# TS-ARM3_0_6.net
KiCad netlist of a schematic drawn in EAGLE
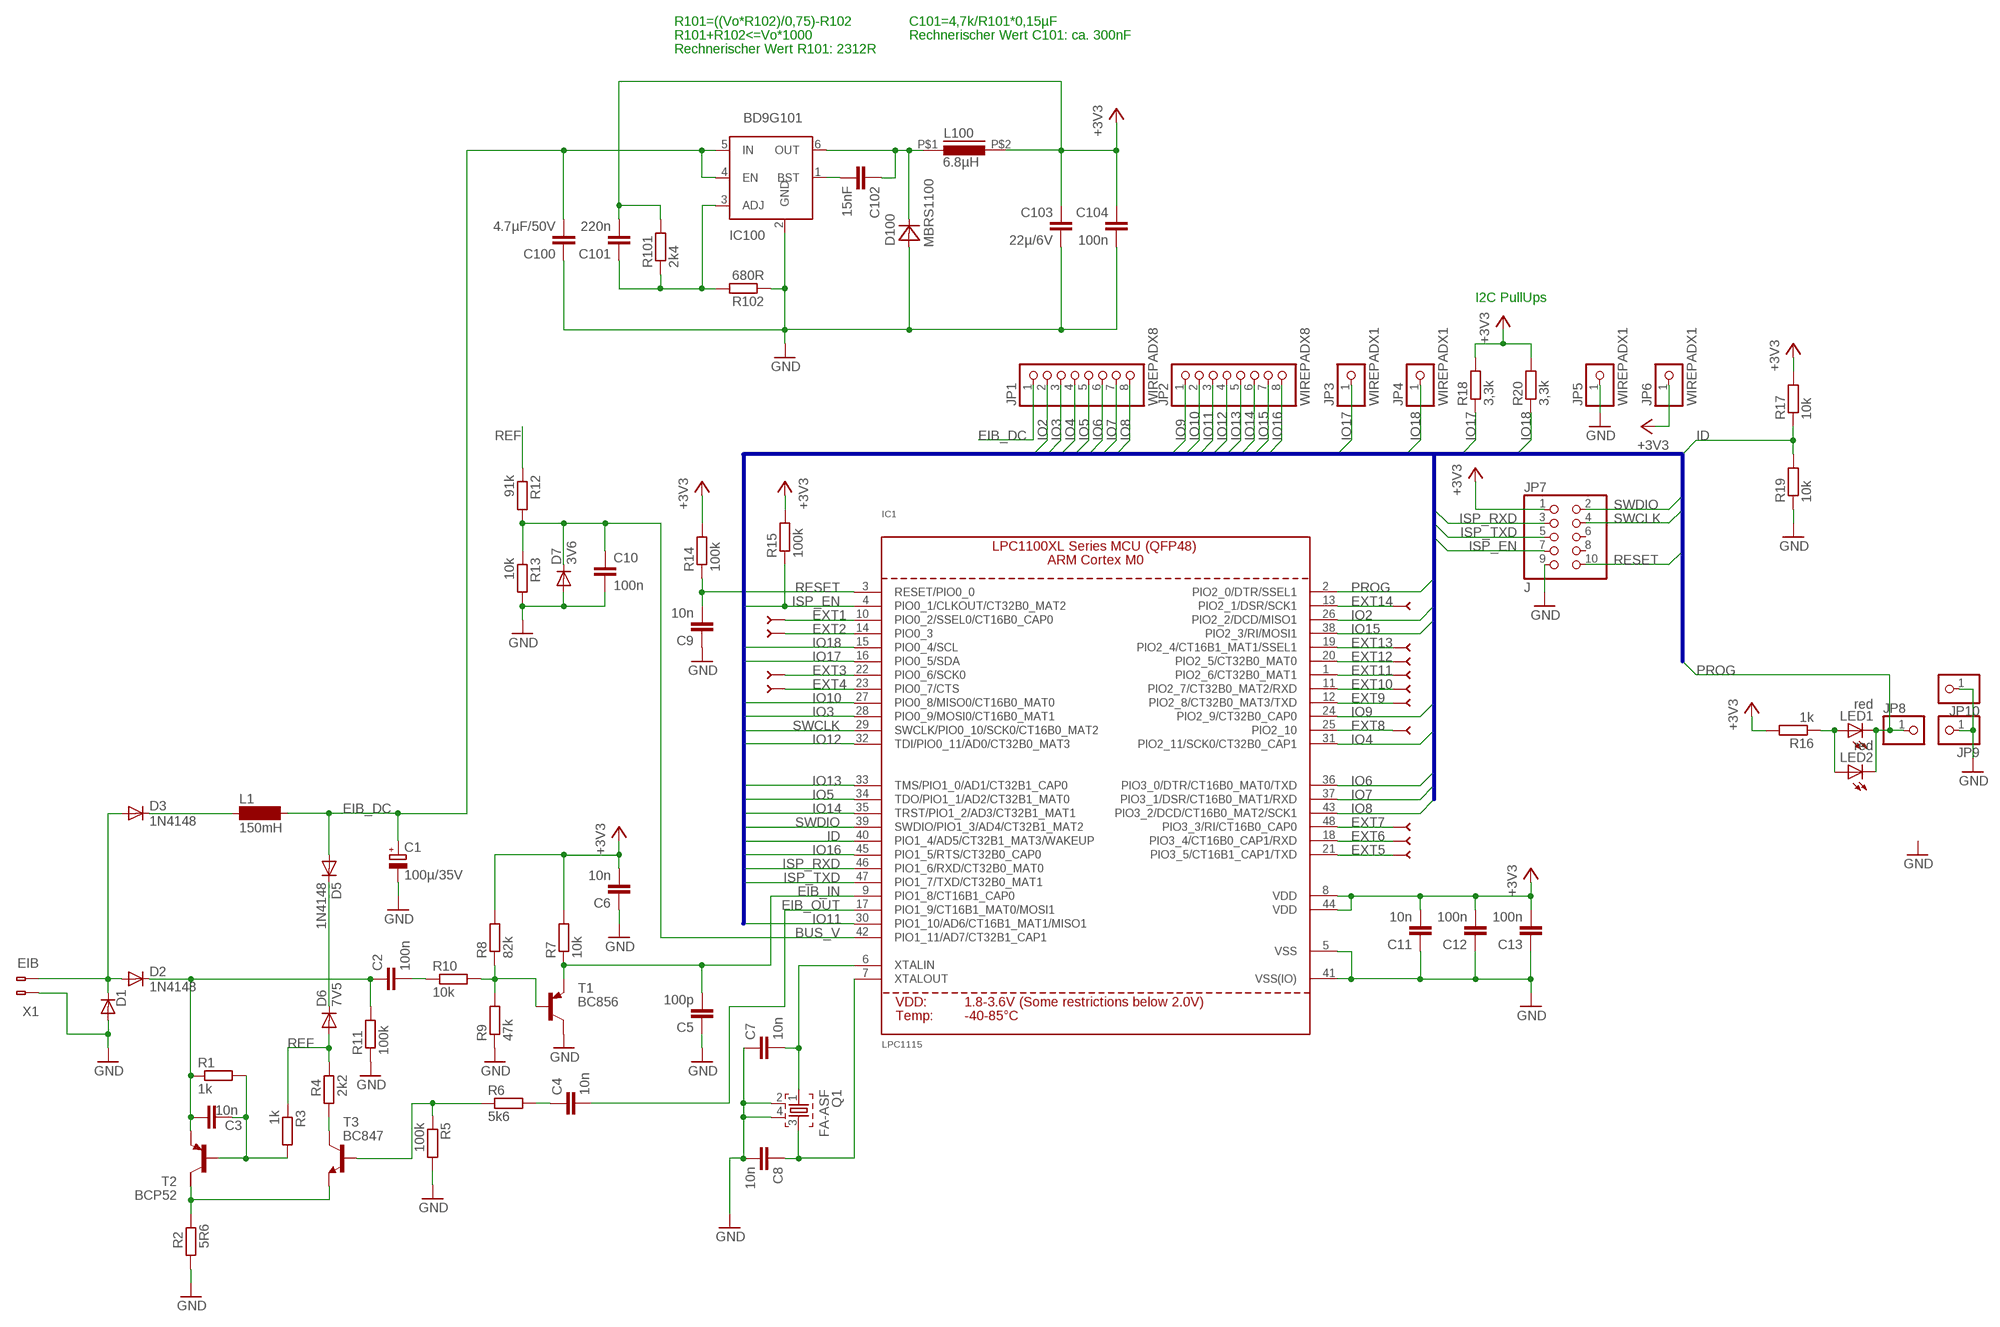
[diagram p0: schematic, sheet 1]

(export (version "E")
  (design (tool "Eeschema 10.0.6"))
  (components
    (comp (ref "C1")
      (value "100µ/35V")
      (footprint "eagle-import:SANYO-OSCON_SMD_C6")
      (libsource (lib "eagle-import") (part "CPOL-EUSANYO_SMD_C6"))
    )
    (comp (ref "C2")
      (value "100n")
      (footprint "eagle-import:C1206")
      (libsource (lib "eagle-import") (part "C-EUC1206"))
    )
    (comp (ref "C3")
      (value "10n")
      (footprint "eagle-import:C1206")
      (libsource (lib "eagle-import") (part "C-EUC1206"))
    )
    (comp (ref "C4")
      (value "10n")
      (footprint "eagle-import:C1206")
      (libsource (lib "eagle-import") (part "C-EUC1206"))
    )
    (comp (ref "C5")
      (value "100p")
      (footprint "eagle-import:C1206")
      (libsource (lib "eagle-import") (part "C-EUC1206"))
    )
    (comp (ref "C6")
      (value "10n")
      (footprint "eagle-import:C1206")
      (libsource (lib "eagle-import") (part "C-EUC1206"))
    )
    (comp (ref "C7")
      (value "10n")
      (footprint "eagle-import:C1206")
      (libsource (lib "eagle-import") (part "C-EUC1206"))
    )
    (comp (ref "C8")
      (value "10n")
      (footprint "eagle-import:C1206")
      (libsource (lib "eagle-import") (part "C-EUC1206"))
    )
    (comp (ref "C9")
      (value "10n")
      (footprint "eagle-import:C1206")
      (libsource (lib "eagle-import") (part "C-EUC1206"))
    )
    (comp (ref "C10")
      (value "100n")
      (footprint "eagle-import:C1206")
      (libsource (lib "eagle-import") (part "C-EUC1206"))
    )
    (comp (ref "C11")
      (value "10n")
      (footprint "eagle-import:C1206")
      (libsource (lib "eagle-import") (part "C-EUC1206"))
    )
    (comp (ref "C12")
      (value "100n")
      (footprint "eagle-import:C1206")
      (libsource (lib "eagle-import") (part "C-EUC1206"))
    )
    (comp (ref "C13")
      (value "100n")
      (footprint "eagle-import:C1206")
      (libsource (lib "eagle-import") (part "C-EUC1206"))
    )
    (comp (ref "C100")
      (value "4.7µF/50V")
      (footprint "eagle-import:C1206")
      (libsource (lib "eagle-import") (part "C-EUC1206"))
    )
    (comp (ref "C101")
      (value "220n")
      (footprint "eagle-import:C1206")
      (libsource (lib "eagle-import") (part "C-EUC1206"))
    )
    (comp (ref "C102")
      (value "15nF")
      (footprint "eagle-import:C1206")
      (libsource (lib "eagle-import") (part "C-EUC1206"))
    )
    (comp (ref "C103")
      (value "22µ/6V")
      (footprint "eagle-import:C1206")
      (libsource (lib "eagle-import") (part "C-EUC1206"))
    )
    (comp (ref "C104")
      (value "100n")
      (footprint "eagle-import:C1206")
      (libsource (lib "eagle-import") (part "C-EUC1206"))
    )
    (comp (ref "D1")
      (value "SMAJ40C")
      (footprint "eagle-import:SMB")
      (libsource (lib "eagle-import") (part "D-SMB"))
    )
    (comp (ref "D2")
      (value "1N4148")
      (footprint "eagle-import:MINIMELF")
      (libsource (lib "eagle-import") (part "DIODE-MINIMELF"))
    )
    (comp (ref "D3")
      (value "1N4148")
      (footprint "eagle-import:MINIMELF")
      (libsource (lib "eagle-import") (part "DIODE-MINIMELF"))
    )
    (comp (ref "D5")
      (value "1N4148")
      (footprint "eagle-import:MINIMELF")
      (libsource (lib "eagle-import") (part "DIODE-MINIMELF"))
    )
    (comp (ref "D6")
      (value "7V5")
      (footprint "eagle-import:MINIMELF")
      (libsource (lib "eagle-import") (part "DIODE-MINIMELF"))
    )
    (comp (ref "D7")
      (value "3V6")
      (footprint "eagle-import:MINIMELF")
      (libsource (lib "eagle-import") (part "DIODE-MINIMELF"))
    )
    (comp (ref "D100")
      (value "MBRS1100")
      (footprint "eagle-import:SMA")
      (libsource (lib "eagle-import") (part "MBRA340T3"))
    )
    (comp (ref "IC1")
      (value "LPC1115")
      (footprint "eagle-import:LQFP48")
      (libsource (lib "eagle-import") (part "LPC1113/4/5_QFP48_XLSERIES"))
    )
    (comp (ref "IC100")
      (value "BD9G101")
      (footprint "eagle-import:SOT23-6")
      (libsource (lib "eagle-import") (part "BD9G101GBD9G101G-SOT23-6"))
    )
    (comp (ref "JP1")
      (value "WIREPADX8")
      (footprint "eagle-import:SMD1,27X2,54X8")
      (libsource (lib "eagle-import") (part "WIREPADX8"))
    )
    (comp (ref "JP2")
      (value "WIREPADX8")
      (footprint "eagle-import:SMD1,27X2,54X8")
      (libsource (lib "eagle-import") (part "WIREPADX8"))
    )
    (comp (ref "JP3")
      (value "WIREPADX1")
      (footprint "eagle-import:SMD1,27X2,54")
      (libsource (lib "eagle-import") (part "WIREPADX1"))
    )
    (comp (ref "JP4")
      (value "WIREPADX1")
      (footprint "eagle-import:SMD1,27X2,54")
      (libsource (lib "eagle-import") (part "WIREPADX1"))
    )
    (comp (ref "JP5")
      (value "WIREPADX1")
      (footprint "eagle-import:SMD1,27X2,54")
      (libsource (lib "eagle-import") (part "WIREPADX1"))
    )
    (comp (ref "JP6")
      (value "WIREPADX1")
      (footprint "eagle-import:SMD1,27X2,54")
      (libsource (lib "eagle-import") (part "WIREPADX1"))
    )
    (comp (ref "JP7")
      (value "J")
      (footprint "eagle-import:2X05M")
      (libsource (lib "eagle-import") (part "PINHD-2X05_2.00"))
    )
    (comp (ref "JP8")
      (value "PINHD-1X1")
      (footprint "eagle-import:1X01")
      (libsource (lib "eagle-import") (part "PINHD-1X1"))
    )
    (comp (ref "JP9")
      (value "PINHD-1X1")
      (footprint "eagle-import:1X01")
      (libsource (lib "eagle-import") (part "PINHD-1X1"))
    )
    (comp (ref "JP10")
      (value "PINHD-1X1")
      (footprint "eagle-import:1X01")
      (libsource (lib "eagle-import") (part "PINHD-1X1"))
    )
    (comp (ref "L1")
      (value "150mH")
      (footprint "eagle-import:SD12_1000")
      (libsource (lib "eagle-import") (part "SD12-1000"))
    )
    (comp (ref "L100")
      (value "6.8µH")
      (footprint "eagle-import:PIS2812")
      (libsource (lib "eagle-import") (part "IND_FASTRON_1616FPS"))
    )
    (comp (ref "LED1")
      (value "red")
      (footprint "eagle-import:CHIPLED_1206")
      (libsource (lib "eagle-import") (part "LEDCHIPLED_1206"))
    )
    (comp (ref "LED2")
      (value "red")
      (footprint "eagle-import:LED3MM")
      (libsource (lib "eagle-import") (part "LED3MM"))
    )
    (comp (ref "P1")
      (value "PAD")
      (footprint "eagle-import:PAD")
      (libsource (lib "eagle-import") (part "PAD"))
    )
    (comp (ref "P2")
      (value "PAD")
      (footprint "eagle-import:PAD")
      (libsource (lib "eagle-import") (part "PAD"))
    )
    (comp (ref "P3")
      (value "PAD")
      (footprint "eagle-import:PAD")
      (libsource (lib "eagle-import") (part "PAD"))
    )
    (comp (ref "P4")
      (value "PAD")
      (footprint "eagle-import:PAD")
      (libsource (lib "eagle-import") (part "PAD"))
    )
    (comp (ref "P5")
      (value "PAD")
      (footprint "eagle-import:PAD")
      (libsource (lib "eagle-import") (part "PAD"))
    )
    (comp (ref "P6")
      (value "PAD")
      (footprint "eagle-import:PAD")
      (libsource (lib "eagle-import") (part "PAD"))
    )
    (comp (ref "P7")
      (value "PAD")
      (footprint "eagle-import:PAD")
      (libsource (lib "eagle-import") (part "PAD"))
    )
    (comp (ref "P8")
      (value "PAD")
      (footprint "eagle-import:PAD")
      (libsource (lib "eagle-import") (part "PAD"))
    )
    (comp (ref "P9")
      (value "PAD")
      (footprint "eagle-import:PAD")
      (libsource (lib "eagle-import") (part "PAD"))
    )
    (comp (ref "P10")
      (value "PAD")
      (footprint "eagle-import:PAD")
      (libsource (lib "eagle-import") (part "PAD"))
    )
    (comp (ref "P11")
      (value "PAD")
      (footprint "eagle-import:PAD")
      (libsource (lib "eagle-import") (part "PAD"))
    )
    (comp (ref "P12")
      (value "PAD")
      (footprint "eagle-import:PAD")
      (libsource (lib "eagle-import") (part "PAD"))
    )
    (comp (ref "P13")
      (value "PAD")
      (footprint "eagle-import:PAD")
      (libsource (lib "eagle-import") (part "PAD"))
    )
    (comp (ref "P14")
      (value "PAD")
      (footprint "eagle-import:PAD")
      (libsource (lib "eagle-import") (part "PAD"))
    )
    (comp (ref "Q1")
      (value "FA-ASF")
      (footprint "eagle-import:ASF")
      (libsource (lib "eagle-import") (part "FA-ASF"))
    )
    (comp (ref "R1")
      (value "1k")
      (footprint "eagle-import:R1206")
      (libsource (lib "eagle-import") (part "R-EU_R1206"))
    )
    (comp (ref "R2")
      (value "5R6")
      (footprint "eagle-import:R1206")
      (libsource (lib "eagle-import") (part "R-EU_R1206"))
    )
    (comp (ref "R3")
      (value "1k")
      (footprint "eagle-import:R1206")
      (libsource (lib "eagle-import") (part "R-EU_R1206"))
    )
    (comp (ref "R4")
      (value "2k2")
      (footprint "eagle-import:R1206")
      (libsource (lib "eagle-import") (part "R-EU_R1206"))
    )
    (comp (ref "R5")
      (value "100k")
      (footprint "eagle-import:R1206")
      (libsource (lib "eagle-import") (part "R-EU_R1206"))
    )
    (comp (ref "R6")
      (value "5k6")
      (footprint "eagle-import:R1206")
      (libsource (lib "eagle-import") (part "R-EU_R1206"))
    )
    (comp (ref "R7")
      (value "10k")
      (footprint "eagle-import:R1206")
      (libsource (lib "eagle-import") (part "R-EU_R1206"))
    )
    (comp (ref "R8")
      (value "82k")
      (footprint "eagle-import:R1206")
      (libsource (lib "eagle-import") (part "R-EU_R1206"))
    )
    (comp (ref "R9")
      (value "47k")
      (footprint "eagle-import:R1206")
      (libsource (lib "eagle-import") (part "R-EU_R1206"))
    )
    (comp (ref "R10")
      (value "10k")
      (footprint "eagle-import:R1206")
      (libsource (lib "eagle-import") (part "R-EU_R1206"))
    )
    (comp (ref "R11")
      (value "100k")
      (footprint "eagle-import:R1206")
      (libsource (lib "eagle-import") (part "R-EU_R1206"))
    )
    (comp (ref "R12")
      (value "91k")
      (footprint "eagle-import:R1206")
      (libsource (lib "eagle-import") (part "R-EU_R1206"))
    )
    (comp (ref "R13")
      (value "10k")
      (footprint "eagle-import:R1206")
      (libsource (lib "eagle-import") (part "R-EU_R1206"))
    )
    (comp (ref "R14")
      (value "100k")
      (footprint "eagle-import:R1206")
      (libsource (lib "eagle-import") (part "R-EU_R1206"))
    )
    (comp (ref "R15")
      (value "100k")
      (footprint "eagle-import:R1206")
      (libsource (lib "eagle-import") (part "R-EU_R1206"))
    )
    (comp (ref "R16")
      (value "1k")
      (footprint "eagle-import:R1206")
      (libsource (lib "eagle-import") (part "R-EU_R1206"))
    )
    (comp (ref "R17")
      (value "10k")
      (footprint "eagle-import:R1206")
      (libsource (lib "eagle-import") (part "R-EU_R1206"))
    )
    (comp (ref "R18")
      (value "3,3k")
      (footprint "eagle-import:R1206")
      (libsource (lib "eagle-import") (part "R-EU_R1206"))
    )
    (comp (ref "R19")
      (value "10k")
      (footprint "eagle-import:R1206")
      (libsource (lib "eagle-import") (part "R-EU_R1206"))
    )
    (comp (ref "R20")
      (value "3,3k")
      (footprint "eagle-import:R1206")
      (libsource (lib "eagle-import") (part "R-EU_R1206"))
    )
    (comp (ref "R101")
      (value "2k4")
      (footprint "eagle-import:R1206")
      (libsource (lib "eagle-import") (part "R-EU_R1206"))
    )
    (comp (ref "R102")
      (value "680R")
      (footprint "eagle-import:R1206")
      (libsource (lib "eagle-import") (part "R-EU_R1206"))
    )
    (comp (ref "T1")
      (value "BC856")
      (footprint "eagle-import:SOT23-BEC")
      (libsource (lib "eagle-import") (part "BC856SMDB"))
    )
    (comp (ref "T2")
      (value "BCP52")
      (footprint "eagle-import:SOT223")
      (libsource (lib "eagle-import") (part "FZT753SMD"))
    )
    (comp (ref "T3")
      (value "BC847")
      (footprint "eagle-import:SOT23")
      (libsource (lib "eagle-import") (part "BC847"))
    )
    (comp (ref "X1")
      (value "EIB")
      (footprint "eagle-import:BUSKLEMME243-724")
      (libsource (lib "eagle-import") (part "EIB"))
    )
  )
  (nets
    (net (code "1") (name "+3V3") (class "Default")
      (node (ref "C101") (pin "2") (pinfunction "2_2") (pintype "passive"))
      (node (ref "C103") (pin "1") (pinfunction "1_1") (pintype "passive"))
      (node (ref "C104") (pin "1") (pinfunction "1_1") (pintype "passive"))
      (node (ref "C11") (pin "2") (pinfunction "2_2") (pintype "passive"))
      (node (ref "C12") (pin "2") (pinfunction "2_2") (pintype "passive"))
      (node (ref "C13") (pin "2") (pinfunction "2_2") (pintype "passive"))
      (node (ref "C6") (pin "2") (pinfunction "2_2") (pintype "passive"))
      (node (ref "IC1") (pin "44") (pinfunction "VDD_44") (pintype "power_in"))
      (node (ref "IC1") (pin "8") (pinfunction "VDD_8") (pintype "power_in"))
      (node (ref "JP6") (pin "1") (pinfunction "1_1") (pintype "passive"))
      (node (ref "JP7") (pin "1") (pinfunction "1_1") (pintype "passive"))
      (node (ref "L100") (pin "P$2") (pinfunction "2_P$2") (pintype "passive"))
      (node (ref "R101") (pin "2") (pinfunction "2_2") (pintype "passive"))
      (node (ref "R14") (pin "2") (pinfunction "2_2") (pintype "passive"))
      (node (ref "R15") (pin "2") (pinfunction "2_2") (pintype "passive"))
      (node (ref "R16") (pin "2") (pinfunction "2_2") (pintype "passive"))
      (node (ref "R17") (pin "2") (pinfunction "2_2") (pintype "passive"))
      (node (ref "R18") (pin "2") (pinfunction "2_2") (pintype "passive"))
      (node (ref "R20") (pin "2") (pinfunction "2_2") (pintype "passive"))
      (node (ref "R7") (pin "2") (pinfunction "2_2") (pintype "passive"))
      (node (ref "R8") (pin "2") (pinfunction "2_2") (pintype "passive"))
    )
    (net (code "2") (name "/BUS_V") (class "Default")
      (node (ref "C10") (pin "2") (pinfunction "2_2") (pintype "passive"))
      (node (ref "D7") (pin "C") (pinfunction "C_C") (pintype "passive"))
      (node (ref "IC1") (pin "42") (pinfunction "PIO1_11/AD7/CT32B1_CAP1_42") (pintype "bidirectional"))
      (node (ref "R12") (pin "2") (pinfunction "2_2") (pintype "passive"))
      (node (ref "R13") (pin "1") (pinfunction "1_1") (pintype "passive"))
    )
    (net (code "3") (name "/EIB_DC") (class "Default")
      (node (ref "C1") (pin "+") (pinfunction "+_+") (pintype "passive"))
      (node (ref "C100") (pin "2") (pinfunction "2_2") (pintype "passive"))
      (node (ref "D5") (pin "A") (pinfunction "A_A") (pintype "passive"))
      (node (ref "IC100") (pin "4") (pinfunction "EN_4") (pintype "input"))
      (node (ref "IC100") (pin "5") (pinfunction "IN_5") (pintype "input"))
      (node (ref "JP1") (pin "1") (pinfunction "1_1") (pintype "passive"))
      (node (ref "L1") (pin "2") (pinfunction "2_2") (pintype "passive"))
    )
    (net (code "4") (name "/EIB_IN") (class "Default")
      (node (ref "C5") (pin "2") (pinfunction "2_2") (pintype "passive"))
      (node (ref "IC1") (pin "9") (pinfunction "PIO1_8/CT16B1_CAP0_9") (pintype "bidirectional"))
      (node (ref "R7") (pin "1") (pinfunction "1_1") (pintype "passive"))
      (node (ref "T1") (pin "E") (pinfunction "E_E") (pintype "passive"))
    )
    (net (code "5") (name "/EIB_OUT") (class "Default")
      (node (ref "C4") (pin "2") (pinfunction "2_2") (pintype "passive"))
      (node (ref "IC1") (pin "17") (pinfunction "PIO1_9/CT16B1_MAT0/MOSI1_17") (pintype "bidirectional"))
    )
    (net (code "6") (name "/EXT1") (class "Default")
      (node (ref "IC1") (pin "10") (pinfunction "PIO0_2/SSEL0/CT16B0_CAP0_10") (pintype "bidirectional"))
      (node (ref "P1") (pin "1") (pinfunction "1_1") (pintype "bidirectional"))
    )
    (net (code "7") (name "/EXT2") (class "Default")
      (node (ref "IC1") (pin "14") (pinfunction "PIO0_3_14") (pintype "bidirectional"))
      (node (ref "P2") (pin "1") (pinfunction "1_1") (pintype "bidirectional"))
    )
    (net (code "8") (name "/EXT3") (class "Default")
      (node (ref "IC1") (pin "22") (pinfunction "PIO0_6/SCK0_22") (pintype "bidirectional"))
      (node (ref "P13") (pin "1") (pinfunction "1_1") (pintype "bidirectional"))
    )
    (net (code "9") (name "/EXT4") (class "Default")
      (node (ref "IC1") (pin "23") (pinfunction "PIO0_7/CTS_23") (pintype "bidirectional"))
      (node (ref "P14") (pin "1") (pinfunction "1_1") (pintype "bidirectional"))
    )
    (net (code "10") (name "/EXT5") (class "Default")
      (node (ref "IC1") (pin "21") (pinfunction "PIO3_5/CT16B1_CAP1/TXD_21") (pintype "bidirectional"))
      (node (ref "P12") (pin "1") (pinfunction "1_1") (pintype "bidirectional"))
    )
    (net (code "11") (name "/EXT6") (class "Default")
      (node (ref "IC1") (pin "18") (pinfunction "PIO3_4/CT16B0_CAP1/RXD_18") (pintype "bidirectional"))
      (node (ref "P11") (pin "1") (pinfunction "1_1") (pintype "bidirectional"))
    )
    (net (code "12") (name "/EXT7") (class "Default")
      (node (ref "IC1") (pin "48") (pinfunction "PIO3_3/RI/CT16B0_CAP0_48") (pintype "bidirectional"))
      (node (ref "P10") (pin "1") (pinfunction "1_1") (pintype "bidirectional"))
    )
    (net (code "13") (name "/EXT8") (class "Default")
      (node (ref "IC1") (pin "25") (pinfunction "PIO2_10_25") (pintype "bidirectional"))
      (node (ref "P6") (pin "1") (pinfunction "1_1") (pintype "bidirectional"))
    )
    (net (code "14") (name "/EXT9") (class "Default")
      (node (ref "IC1") (pin "12") (pinfunction "PIO2_8/CT32B0_MAT3/TXD_12") (pintype "bidirectional"))
      (node (ref "P4") (pin "1") (pinfunction "1_1") (pintype "bidirectional"))
    )
    (net (code "15") (name "/EXT10") (class "Default")
      (node (ref "IC1") (pin "11") (pinfunction "PIO2_7/CT32B0_MAT2/RXD_11") (pintype "bidirectional"))
      (node (ref "P5") (pin "1") (pinfunction "1_1") (pintype "bidirectional"))
    )
    (net (code "16") (name "/EXT11") (class "Default")
      (node (ref "IC1") (pin "1") (pinfunction "PIO2_6/CT32B0_MAT1_1") (pintype "bidirectional"))
      (node (ref "P9") (pin "1") (pinfunction "1_1") (pintype "bidirectional"))
    )
    (net (code "17") (name "/EXT12") (class "Default")
      (node (ref "IC1") (pin "20") (pinfunction "PIO2_5/CT32B0_MAT0_20") (pintype "bidirectional"))
      (node (ref "P8") (pin "1") (pinfunction "1_1") (pintype "bidirectional"))
    )
    (net (code "18") (name "/EXT13") (class "Default")
      (node (ref "IC1") (pin "19") (pinfunction "PIO2_4/CT16B1_MAT1/SSEL1_19") (pintype "bidirectional"))
      (node (ref "P7") (pin "1") (pinfunction "1_1") (pintype "bidirectional"))
    )
    (net (code "19") (name "/EXT14") (class "Default")
      (node (ref "IC1") (pin "13") (pinfunction "PIO2_1/DSR/SCK1_13") (pintype "bidirectional"))
      (node (ref "P3") (pin "1") (pinfunction "1_1") (pintype "bidirectional"))
    )
    (net (code "20") (name "/ID") (class "Default")
      (node (ref "IC1") (pin "40") (pinfunction "PIO1_4/AD5/CT32B1_MAT3/WAKEUP_40") (pintype "bidirectional"))
      (node (ref "R17") (pin "1") (pinfunction "1_1") (pintype "passive"))
      (node (ref "R19") (pin "2") (pinfunction "2_2") (pintype "passive"))
    )
    (net (code "21") (name "/IO2") (class "Default")
      (node (ref "IC1") (pin "26") (pinfunction "PIO2_2/DCD/MISO1_26") (pintype "bidirectional"))
      (node (ref "JP1") (pin "2") (pinfunction "2_2") (pintype "passive"))
    )
    (net (code "22") (name "/IO3") (class "Default")
      (node (ref "IC1") (pin "28") (pinfunction "PIO0_9/MOSI0/CT16B0_MAT1_28") (pintype "bidirectional"))
      (node (ref "JP1") (pin "3") (pinfunction "3_3") (pintype "passive"))
    )
    (net (code "23") (name "/IO4") (class "Default")
      (node (ref "IC1") (pin "31") (pinfunction "PIO2_11/SCK0/CT32B0_CAP1_31") (pintype "bidirectional"))
      (node (ref "JP1") (pin "4") (pinfunction "4_4") (pintype "passive"))
    )
    (net (code "24") (name "/IO5") (class "Default")
      (node (ref "IC1") (pin "34") (pinfunction "TDO/PIO1_1/AD2/CT32B1_MAT0_34") (pintype "bidirectional"))
      (node (ref "JP1") (pin "5") (pinfunction "5_5") (pintype "passive"))
    )
    (net (code "25") (name "/IO6") (class "Default")
      (node (ref "IC1") (pin "36") (pinfunction "PIO3_0/DTR/CT16B0_MAT0/TXD_36") (pintype "bidirectional"))
      (node (ref "JP1") (pin "6") (pinfunction "6_6") (pintype "passive"))
    )
    (net (code "26") (name "/IO7") (class "Default")
      (node (ref "IC1") (pin "37") (pinfunction "PIO3_1/DSR/CT16B0_MAT1/RXD_37") (pintype "bidirectional"))
      (node (ref "JP1") (pin "7") (pinfunction "7_7") (pintype "passive"))
    )
    (net (code "27") (name "/IO8") (class "Default")
      (node (ref "IC1") (pin "43") (pinfunction "PIO3_2/DCD/CT16B0_MAT2/SCK1_43") (pintype "bidirectional"))
      (node (ref "JP1") (pin "8") (pinfunction "8_8") (pintype "passive"))
    )
    (net (code "28") (name "/IO9") (class "Default")
      (node (ref "IC1") (pin "24") (pinfunction "PIO2_9/CT32B0_CAP0_24") (pintype "bidirectional"))
      (node (ref "JP2") (pin "1") (pinfunction "1_1") (pintype "passive"))
    )
    (net (code "29") (name "/IO10") (class "Default")
      (node (ref "IC1") (pin "27") (pinfunction "PIO0_8/MISO0/CT16B0_MAT0_27") (pintype "bidirectional"))
      (node (ref "JP2") (pin "2") (pinfunction "2_2") (pintype "passive"))
    )
    (net (code "30") (name "/IO11") (class "Default")
      (node (ref "IC1") (pin "30") (pinfunction "PIO1_10/AD6/CT16B1_MAT1/MISO1_30") (pintype "bidirectional"))
      (node (ref "JP2") (pin "3") (pinfunction "3_3") (pintype "passive"))
    )
    (net (code "31") (name "/IO12") (class "Default")
      (node (ref "IC1") (pin "32") (pinfunction "TDI/PIO0_11/AD0/CT32B0_MAT3_32") (pintype "bidirectional"))
      (node (ref "JP2") (pin "4") (pinfunction "4_4") (pintype "passive"))
    )
    (net (code "32") (name "/IO13") (class "Default")
      (node (ref "IC1") (pin "33") (pinfunction "TMS/PIO1_0/AD1/CT32B1_CAP0_33") (pintype "bidirectional"))
      (node (ref "JP2") (pin "5") (pinfunction "5_5") (pintype "passive"))
    )
    (net (code "33") (name "/IO14") (class "Default")
      (node (ref "IC1") (pin "35") (pinfunction "TRST/PIO1_2/AD3/CT32B1_MAT1_35") (pintype "bidirectional"))
      (node (ref "JP2") (pin "6") (pinfunction "6_6") (pintype "passive"))
    )
    (net (code "34") (name "/IO15") (class "Default")
      (node (ref "IC1") (pin "38") (pinfunction "PIO2_3/RI/MOSI1_38") (pintype "bidirectional"))
      (node (ref "JP2") (pin "7") (pinfunction "7_7") (pintype "passive"))
    )
    (net (code "35") (name "/IO16") (class "Default")
      (node (ref "IC1") (pin "45") (pinfunction "PIO1_5/RTS/CT32B0_CAP0_45") (pintype "bidirectional"))
      (node (ref "JP2") (pin "8") (pinfunction "8_8") (pintype "passive"))
    )
    (net (code "36") (name "/IO17") (class "Default")
      (node (ref "IC1") (pin "16") (pinfunction "PIO0_5/SDA_16") (pintype "bidirectional"))
      (node (ref "JP3") (pin "1") (pinfunction "1_1") (pintype "passive"))
      (node (ref "R18") (pin "1") (pinfunction "1_1") (pintype "passive"))
    )
    (net (code "37") (name "/IO18") (class "Default")
      (node (ref "IC1") (pin "15") (pinfunction "PIO0_4/SCL_15") (pintype "bidirectional"))
      (node (ref "JP4") (pin "1") (pinfunction "1_1") (pintype "passive"))
      (node (ref "R20") (pin "1") (pinfunction "1_1") (pintype "passive"))
    )
    (net (code "38") (name "/ISP_EN") (class "Default")
      (node (ref "IC1") (pin "4") (pinfunction "PIO0_1/CLKOUT/CT32B0_MAT2_4") (pintype "bidirectional"))
      (node (ref "JP7") (pin "7") (pinfunction "7_7") (pintype "passive"))
      (node (ref "R15") (pin "1") (pinfunction "1_1") (pintype "passive"))
    )
    (net (code "39") (name "/ISP_RXD") (class "Default")
      (node (ref "IC1") (pin "46") (pinfunction "PIO1_6/RXD/CT32B0_MAT0_46") (pintype "bidirectional"))
      (node (ref "JP7") (pin "3") (pinfunction "3_3") (pintype "passive"))
    )
    (net (code "40") (name "/ISP_TXD") (class "Default")
      (node (ref "IC1") (pin "47") (pinfunction "PIO1_7/TXD/CT32B0_MAT1_47") (pintype "bidirectional"))
      (node (ref "JP7") (pin "5") (pinfunction "5_5") (pintype "passive"))
    )
    (net (code "41") (name "/PROG") (class "Default")
      (node (ref "IC1") (pin "2") (pinfunction "PIO2_0/DTR/SSEL1_2") (pintype "bidirectional"))
      (node (ref "JP8") (pin "1") (pinfunction "1_1") (pintype "passive"))
      (node (ref "LED1") (pin "C") (pinfunction "C_C") (pintype "passive"))
      (node (ref "LED2") (pin "K") (pinfunction "C_K") (pintype "passive"))
    )
    (net (code "42") (name "/REF") (class "Default")
      (node (ref "D6") (pin "A") (pinfunction "A_A") (pintype "passive"))
      (node (ref "R12") (pin "1") (pinfunction "1_1") (pintype "passive"))
      (node (ref "R3") (pin "1") (pinfunction "1_1") (pintype "passive"))
      (node (ref "R4") (pin "2") (pinfunction "2_2") (pintype "passive"))
    )
    (net (code "43") (name "/RESET") (class "Default")
      (node (ref "C9") (pin "2") (pinfunction "2_2") (pintype "passive"))
      (node (ref "IC1") (pin "3") (pinfunction "RESET/PIO0_0_3") (pintype "bidirectional"))
      (node (ref "JP7") (pin "10") (pinfunction "10_10") (pintype "passive"))
      (node (ref "R14") (pin "1") (pinfunction "1_1") (pintype "passive"))
    )
    (net (code "44") (name "/SWCLK") (class "Default")
      (node (ref "IC1") (pin "29") (pinfunction "SWCLK/PIO0_10/SCK0/CT16B0_MAT2_29") (pintype "bidirectional"))
      (node (ref "JP7") (pin "4") (pinfunction "4_4") (pintype "passive"))
    )
    (net (code "45") (name "/SWDIO") (class "Default")
      (node (ref "IC1") (pin "39") (pinfunction "SWDIO/PIO1_3/AD4/CT32B1_MAT2_39") (pintype "bidirectional"))
      (node (ref "JP7") (pin "2") (pinfunction "2_2") (pintype "passive"))
    )
    (net (code "46") (name "GND") (class "Default")
      (node (ref "C1") (pin "-") (pinfunction "-_-") (pintype "passive"))
      (node (ref "C10") (pin "1") (pinfunction "1_1") (pintype "passive"))
      (node (ref "C100") (pin "1") (pinfunction "1_1") (pintype "passive"))
      (node (ref "C103") (pin "2") (pinfunction "2_2") (pintype "passive"))
      (node (ref "C104") (pin "2") (pinfunction "2_2") (pintype "passive"))
      (node (ref "C11") (pin "1") (pinfunction "1_1") (pintype "passive"))
      (node (ref "C12") (pin "1") (pinfunction "1_1") (pintype "passive"))
      (node (ref "C13") (pin "1") (pinfunction "1_1") (pintype "passive"))
      (node (ref "C5") (pin "1") (pinfunction "1_1") (pintype "passive"))
      (node (ref "C6") (pin "1") (pinfunction "1_1") (pintype "passive"))
      (node (ref "C7") (pin "1") (pinfunction "1_1") (pintype "passive"))
      (node (ref "C8") (pin "2") (pinfunction "2_2") (pintype "passive"))
      (node (ref "C9") (pin "1") (pinfunction "1_1") (pintype "passive"))
      (node (ref "D1") (pin "2") (pinfunction "A_2") (pintype "passive"))
      (node (ref "D100") (pin "A") (pinfunction "A_A") (pintype "passive"))
      (node (ref "D7") (pin "A") (pinfunction "A_A") (pintype "passive"))
      (node (ref "IC1") (pin "41") (pinfunction "VSS(IO)_41") (pintype "power_in"))
      (node (ref "IC1") (pin "5") (pinfunction "VSS_5") (pintype "power_in"))
      (node (ref "IC100") (pin "2") (pinfunction "GND_2") (pintype "power_in"))
      (node (ref "JP10") (pin "1") (pinfunction "1_1") (pintype "passive"))
      (node (ref "JP5") (pin "1") (pinfunction "1_1") (pintype "passive"))
      (node (ref "JP7") (pin "9") (pinfunction "9_9") (pintype "passive"))
      (node (ref "JP9") (pin "1") (pinfunction "1_1") (pintype "passive"))
      (node (ref "Q1") (pin "2") (pinfunction "2_2") (pintype "passive"))
      (node (ref "Q1") (pin "4") (pinfunction "4_4") (pintype "passive"))
      (node (ref "R102") (pin "1") (pinfunction "1_1") (pintype "passive"))
      (node (ref "R11") (pin "1") (pinfunction "1_1") (pintype "passive"))
      (node (ref "R13") (pin "2") (pinfunction "2_2") (pintype "passive"))
      (node (ref "R19") (pin "1") (pinfunction "1_1") (pintype "passive"))
      (node (ref "R2") (pin "1") (pinfunction "1_1") (pintype "passive"))
      (node (ref "R5") (pin "2") (pinfunction "2_2") (pintype "passive"))
      (node (ref "R9") (pin "1") (pinfunction "1_1") (pintype "passive"))
      (node (ref "T1") (pin "C") (pinfunction "C_C") (pintype "passive"))
      (node (ref "X1") (pin "1") (pinfunction "B-1_1") (pintype "passive"))
    )
    (net (code "47") (name "Net-(C2-Pad2)") (class "Default")
      (node (ref "C2") (pin "2") (pinfunction "2_2") (pintype "passive"))
      (node (ref "R10") (pin "1") (pinfunction "1_1") (pintype "passive"))
    )
    (net (code "48") (name "Net-(C4-Pad1)") (class "Default")
      (node (ref "C4") (pin "1") (pinfunction "1_1") (pintype "passive"))
      (node (ref "R6") (pin "2") (pinfunction "2_2") (pintype "passive"))
    )
    (net (code "49") (name "Net-(D1-C)") (class "Default")
      (node (ref "D1") (pin "1") (pinfunction "C_1") (pintype "passive"))
      (node (ref "D2") (pin "A") (pinfunction "A_A") (pintype "passive"))
      (node (ref "D3") (pin "A") (pinfunction "A_A") (pintype "passive"))
      (node (ref "X1") (pin "2") (pinfunction "B-2_2") (pintype "passive"))
    )
    (net (code "50") (name "Net-(D3-PadC)") (class "Default")
      (node (ref "D3") (pin "C") (pinfunction "C_C") (pintype "passive"))
      (node (ref "L1") (pin "1") (pinfunction "1_1") (pintype "passive"))
    )
    (net (code "51") (name "Net-(D5-PadC)") (class "Default")
      (node (ref "D5") (pin "C") (pinfunction "C_C") (pintype "passive"))
      (node (ref "D6") (pin "C") (pinfunction "C_C") (pintype "passive"))
    )
    (net (code "52") (name "Net-(IC1-XTALIN)") (class "Default")
      (node (ref "C7") (pin "2") (pinfunction "2_2") (pintype "passive"))
      (node (ref "IC1") (pin "6") (pinfunction "XTALIN_6") (pintype "input"))
      (node (ref "Q1") (pin "1") (pinfunction "1_1") (pintype "passive"))
    )
    (net (code "53") (name "Net-(IC1-XTALOUT)") (class "Default")
      (node (ref "C8") (pin "1") (pinfunction "1_1") (pintype "passive"))
      (node (ref "IC1") (pin "7") (pinfunction "XTALOUT_7") (pintype "output"))
      (node (ref "Q1") (pin "3") (pinfunction "3_3") (pintype "passive"))
    )
    (net (code "54") (name "Net-(IC100-ADJ)") (class "Default")
      (node (ref "C101") (pin "1") (pinfunction "1_1") (pintype "passive"))
      (node (ref "IC100") (pin "3") (pinfunction "ADJ_3") (pintype "passive"))
      (node (ref "R101") (pin "1") (pinfunction "1_1") (pintype "passive"))
      (node (ref "R102") (pin "2") (pinfunction "2_2") (pintype "passive"))
    )
    (net (code "55") (name "Net-(IC100-BST)") (class "Default")
      (node (ref "C102") (pin "2") (pinfunction "2_2") (pintype "passive"))
      (node (ref "IC100") (pin "1") (pinfunction "BST_1") (pintype "output"))
    )
    (net (code "56") (name "Net-(IC100-OUT)") (class "Default")
      (node (ref "C102") (pin "1") (pinfunction "1_1") (pintype "passive"))
      (node (ref "D100") (pin "C") (pinfunction "C_C") (pintype "passive"))
      (node (ref "IC100") (pin "6") (pinfunction "OUT_6") (pintype "output"))
      (node (ref "L100") (pin "P$1") (pinfunction "1_P$1") (pintype "passive"))
    )
    (net (code "57") (name "Net-(LED1-PadA)") (class "Default")
      (node (ref "LED1") (pin "A") (pinfunction "A_A") (pintype "passive"))
      (node (ref "LED2") (pin "A") (pinfunction "A_A") (pintype "passive"))
      (node (ref "R16") (pin "1") (pinfunction "1_1") (pintype "passive"))
    )
    (net (code "58") (name "Net-(R10-Pad2)") (class "Default")
      (node (ref "R10") (pin "2") (pinfunction "2_2") (pintype "passive"))
      (node (ref "R8") (pin "1") (pinfunction "1_1") (pintype "passive"))
      (node (ref "R9") (pin "2") (pinfunction "2_2") (pintype "passive"))
      (node (ref "T1") (pin "B") (pinfunction "B_B") (pintype "passive"))
    )
    (net (code "59") (name "Net-(T2-B)") (class "Default")
      (node (ref "C3") (pin "2") (pinfunction "2_2") (pintype "passive"))
      (node (ref "R1") (pin "2") (pinfunction "2_2") (pintype "passive"))
      (node (ref "R3") (pin "2") (pinfunction "2_2") (pintype "passive"))
      (node (ref "T2") (pin "1") (pinfunction "B_1") (pintype "passive"))
    )
    (net (code "60") (name "Net-(T2-C)") (class "Default")
      (node (ref "R2") (pin "2") (pinfunction "2_2") (pintype "passive"))
      (node (ref "T2") (pin "2") (pinfunction "C_2") (pintype "passive"))
      (node (ref "T3") (pin "2") (pinfunction "E_2") (pintype "passive"))
    )
    (net (code "61") (name "Net-(T2-E)") (class "Default")
      (node (ref "C2") (pin "1") (pinfunction "1_1") (pintype "passive"))
      (node (ref "C3") (pin "1") (pinfunction "1_1") (pintype "passive"))
      (node (ref "D2") (pin "C") (pinfunction "C_C") (pintype "passive"))
      (node (ref "R1") (pin "1") (pinfunction "1_1") (pintype "passive"))
      (node (ref "R11") (pin "2") (pinfunction "2_2") (pintype "passive"))
      (node (ref "T2") (pin "3") (pinfunction "E_3") (pintype "passive"))
    )
    (net (code "62") (name "Net-(T3-B)") (class "Default")
      (node (ref "R5") (pin "1") (pinfunction "1_1") (pintype "passive"))
      (node (ref "R6") (pin "1") (pinfunction "1_1") (pintype "passive"))
      (node (ref "T3") (pin "1") (pinfunction "B_1") (pintype "passive"))
    )
    (net (code "63") (name "Net-(T3-C)") (class "Default")
      (node (ref "R4") (pin "1") (pinfunction "1_1") (pintype "passive"))
      (node (ref "T3") (pin "3") (pinfunction "C_3") (pintype "passive"))
    )
    (net (code "64") (name "unconnected-(JP7-Pad6)") (class "Default")
      (node (ref "JP7") (pin "6") (pinfunction "6_6") (pintype "passive"))
    )
    (net (code "65") (name "unconnected-(JP7-Pad8)") (class "Default")
      (node (ref "JP7") (pin "8") (pinfunction "8_8") (pintype "passive"))
    )
    (net (code "66") (name "unconnected-(T2-C{slash}-Pad4)") (class "Default")
      (node (ref "T2") (pin "4") (pinfunction "C/_4") (pintype "passive"))
    )
  )
)
